# ReferenceVoltage.net
KiCad netlist of a schematic drawn in Altium Designer
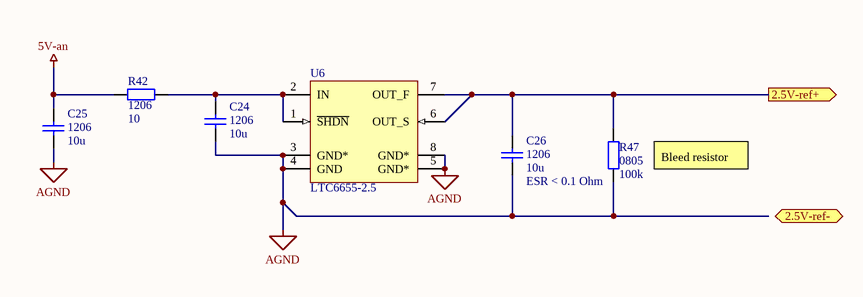
[diagram p0: ReferenceVoltage.SchDoc]

(export (version "E")
  (design (tool "Eeschema 10.0.6"))
  (components
    (comp (ref "C24")
      (value "1206")
      (footprint "SMD_Capacitor_1206")
      (description "Capacitor")
      (fields (field (name "ALTIUM_VALUE") "10u") (field (name "PUBLISHER") "Altium Limited"))
      (libsource (lib "Miscellaneous Devices") (part "Cap"))
    )
    (comp (ref "C25")
      (value "1206")
      (footprint "SMD_Capacitor_1206")
      (description "Capacitor")
      (fields (field (name "ALTIUM_VALUE") "10u") (field (name "PUBLISHER") "Altium Limited"))
      (libsource (lib "Miscellaneous Devices") (part "Cap"))
    )
    (comp (ref "C26")
      (value "ESR < 0.1 Ohm")
      (footprint "SMD_Capacitor_1206")
      (description "Capacitor")
      (fields (field (name "ALTIUM_VALUE") "10u") (field (name "PUBLISHER") "Altium Limited"))
      (libsource (lib "Miscellaneous Devices") (part "Cap"))
    )
    (comp (ref "R42")
      (value "1206")
      (footprint "SMD_Resistor_1206")
      (description "Resistor")
      (fields (field (name "ALTIUM_VALUE") "10") (field (name "PUBLISHER") "Altium Limited"))
      (libsource (lib "") (part "Res2_1"))
    )
    (comp (ref "R47")
      (value "0805")
      (footprint "SMD_Resistor_0805")
      (description "Resistor")
      (fields (field (name "ALTIUM_VALUE") "100k") (field (name "PUBLISHER") "Altium Limited"))
      (libsource (lib "Miscellaneous Devices") (part "Res2"))
    )
    (comp (ref "U6")
      (value "LTC6655-2.5")
      (footprint "MSOP-8")
      (description "0.25ppm Noise, Low Drift  Precision References")
      (libsource (lib "microcircuits_linear-voltage-regulator") (part "LTC6655-2.5"))
    )
  )
  (nets
    (net (code "1") (name "/2.5V-ref+") (class "Default")
      (node (ref "C26") (pin "2") (pinfunction "2_2") (pintype "passive"))
      (node (ref "R47") (pin "2") (pinfunction "2_2") (pintype "passive"))
      (node (ref "U6") (pin "6") (pinfunction "OUT_S_6") (pintype "input"))
      (node (ref "U6") (pin "7") (pinfunction "OUT_F_7") (pintype "power_in"))
    )
    (net (code "3") (name "5V-an") (class "Default")
      (node (ref "C25") (pin "2") (pinfunction "2_2") (pintype "passive"))
      (node (ref "R42") (pin "1") (pinfunction "1_1") (pintype "passive"))
    )
    (net (code "4") (name "AGND") (class "Default")
      (node (ref "C24") (pin "1") (pinfunction "1_1") (pintype "passive"))
      (node (ref "C25") (pin "1") (pinfunction "1_1") (pintype "passive"))
      (node (ref "C26") (pin "1") (pinfunction "1_1") (pintype "passive"))
      (node (ref "R47") (pin "1") (pinfunction "1_1") (pintype "passive"))
      (node (ref "U6") (pin "3") (pinfunction "GND*_3") (pintype "power_in"))
      (node (ref "U6") (pin "4") (pinfunction "GND_4") (pintype "power_in"))
      (node (ref "U6") (pin "5") (pinfunction "GND*_5") (pintype "power_in"))
      (node (ref "U6") (pin "8") (pinfunction "GND*_8") (pintype "power_in"))
    )
    (net (code "5") (name "Net-(U6-IN)") (class "Default")
      (node (ref "C24") (pin "2") (pinfunction "2_2") (pintype "passive"))
      (node (ref "R42") (pin "2") (pinfunction "2_2") (pintype "passive"))
      (node (ref "U6") (pin "1") (pinfunction "~{SHDN}_1") (pintype "input"))
      (node (ref "U6") (pin "2") (pinfunction "IN_2") (pintype "power_in"))
    )
  )
)
